# chcp_schematic.net
KiCad netlist of a schematic drawn in EAGLE
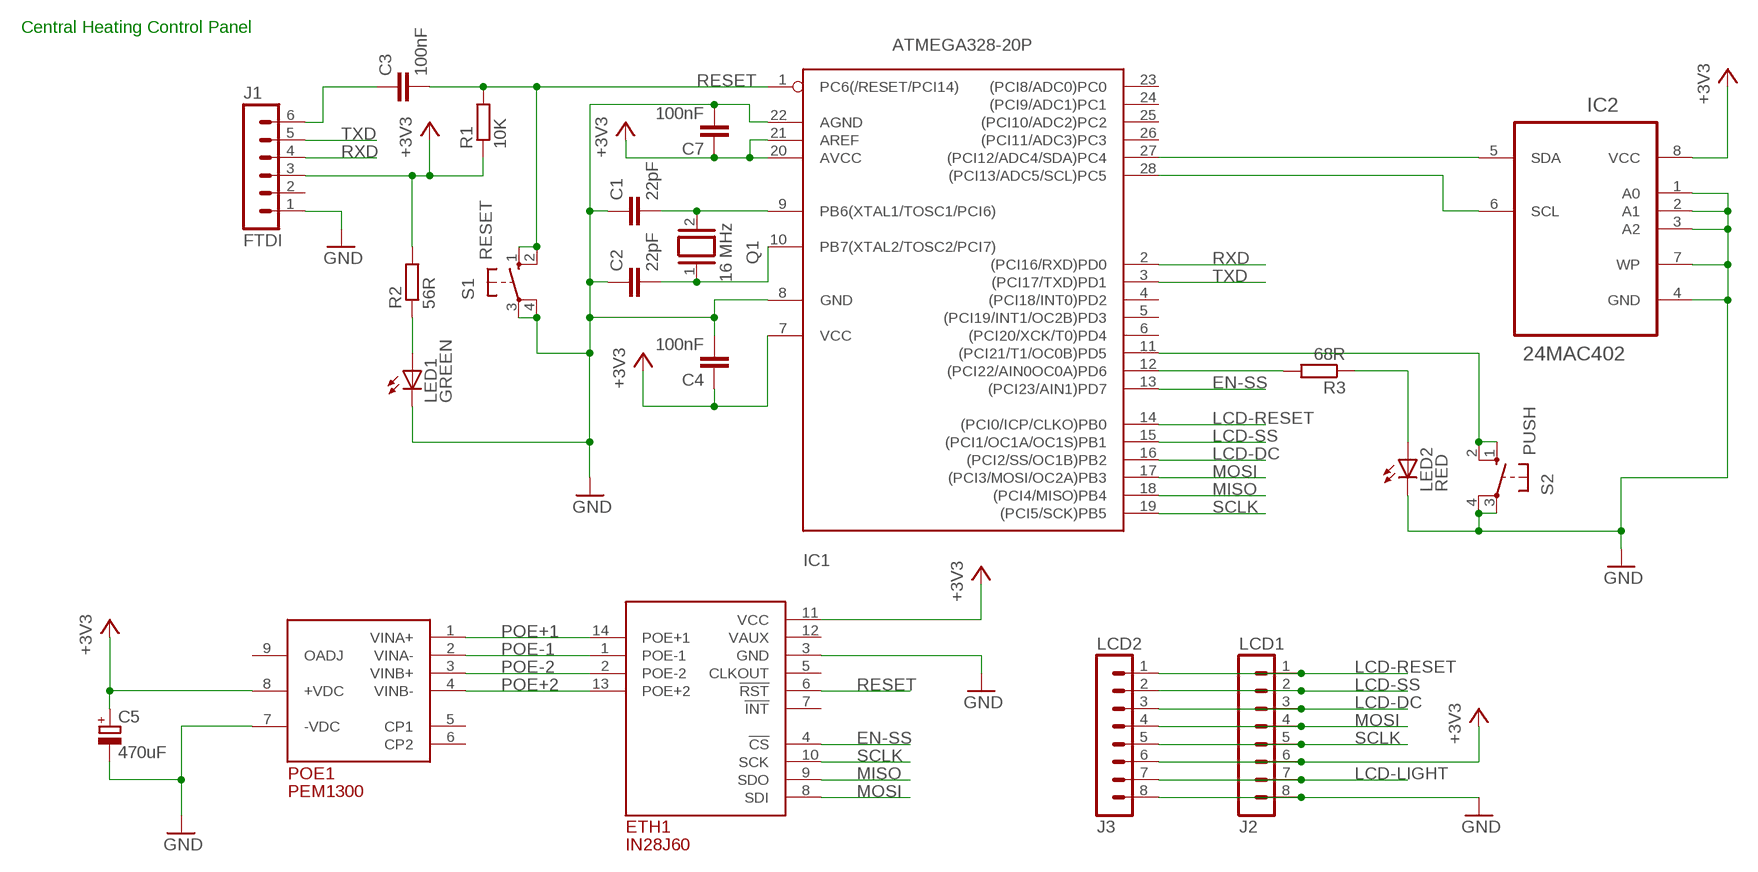
[diagram p0: schematic, sheet 1]

(export (version "E")
  (design (tool "Eeschema 10.0.6"))
  (components
    (comp (ref "C1")
      (value "22pF")
      (footprint "eagle-import:C025-024X044")
      (libsource (lib "eagle-import") (part "C-EU025-024X044"))
    )
    (comp (ref "C2")
      (value "22pF")
      (footprint "eagle-import:C025-024X044")
      (libsource (lib "eagle-import") (part "C-EU025-024X044"))
    )
    (comp (ref "C3")
      (value "100nF")
      (footprint "eagle-import:C025-024X044")
      (libsource (lib "eagle-import") (part "C-EU025-024X044"))
    )
    (comp (ref "C4")
      (value "100nF")
      (footprint "eagle-import:C025-024X044")
      (libsource (lib "eagle-import") (part "C-EU025-024X044"))
    )
    (comp (ref "C5")
      (value "470uF")
      (footprint "eagle-import:E2,5-5")
      (libsource (lib "eagle-import") (part "CPOL-EUE2.5-5"))
    )
    (comp (ref "C7")
      (value "100nF")
      (footprint "eagle-import:C025-024X044")
      (libsource (lib "eagle-import") (part "C-EU025-024X044"))
    )
    (comp (ref "ETH1")
      (value "IN28J60")
      (footprint "eagle-import:DIL")
      (libsource (lib "eagle-import") (part "IN28J60"))
    )
    (comp (ref "IC1")
      (value "ATMEGA328-20P")
      (footprint "eagle-import:DIL28-3")
      (libsource (lib "eagle-import") (part "ATMEGA328P-20"))
    )
    (comp (ref "IC2")
      (value "24MAC402")
      (footprint "eagle-import:PDIP")
      (libsource (lib "eagle-import") (part "24MAC402-SSHM-TPDIP"))
    )
    (comp (ref "J1")
      (value "FTDI")
      (footprint "eagle-import:MA06-1")
      (libsource (lib "eagle-import") (part "MA06-1"))
    )
    (comp (ref "J2")
      (value "LCD1")
      (footprint "eagle-import:MA08-1")
      (libsource (lib "eagle-import") (part "MA08-1"))
    )
    (comp (ref "J3")
      (value "LCD2")
      (footprint "eagle-import:MA08-1")
      (libsource (lib "eagle-import") (part "MA08-1"))
    )
    (comp (ref "LED1")
      (value "GREEN")
      (footprint "eagle-import:LED3MM")
      (libsource (lib "eagle-import") (part "LED3MM"))
    )
    (comp (ref "LED2")
      (value "RED")
      (footprint "eagle-import:LED3MM")
      (libsource (lib "eagle-import") (part "LED3MM"))
    )
    (comp (ref "POE1")
      (value "PEM1300")
      (footprint "eagle-import:SIL")
      (fields (field (name "MPN") "PEM1303"))
      (libsource (lib "eagle-import") (part "PEM1300"))
    )
    (comp (ref "Q1")
      (value "16 MHz")
      (footprint "eagle-import:QS")
      (libsource (lib "eagle-import") (part "XTAL/S"))
    )
    (comp (ref "R1")
      (value "10K")
      (footprint "eagle-import:0204_7")
      (libsource (lib "eagle-import") (part "R-EU_0204/7"))
    )
    (comp (ref "R2")
      (value "56R")
      (footprint "eagle-import:0204_7")
      (libsource (lib "eagle-import") (part "R-EU_0204/7"))
    )
    (comp (ref "R3")
      (value "68R")
      (footprint "eagle-import:0204_7")
      (libsource (lib "eagle-import") (part "R-EU_0204/7"))
    )
    (comp (ref "S1")
      (value "RESET")
      (footprint "eagle-import:B3F-10XX")
      (fields (field (name "MPN") "B3F-1000"))
      (libsource (lib "eagle-import") (part "10-XX"))
    )
    (comp (ref "S2")
      (value "PUSH")
      (footprint "eagle-import:B3F-10XX")
      (fields (field (name "MPN") "B3F-1000"))
      (libsource (lib "eagle-import") (part "10-XX"))
    )
  )
  (nets
    (net (code "1") (name "+3V3") (class "Default")
      (node (ref "C4") (pin "1") (pinfunction "1_1") (pintype "passive"))
      (node (ref "C5") (pin "+") (pinfunction "+_+") (pintype "passive"))
      (node (ref "C7") (pin "1") (pinfunction "1_1") (pintype "passive"))
      (node (ref "ETH1") (pin "11") (pinfunction "VCC_11") (pintype "power_in"))
      (node (ref "IC1") (pin "20") (pinfunction "AVCC_20") (pintype "bidirectional"))
      (node (ref "IC1") (pin "21") (pinfunction "AREF_21") (pintype "bidirectional"))
      (node (ref "IC1") (pin "7") (pinfunction "VCC_7") (pintype "bidirectional"))
      (node (ref "IC2") (pin "8") (pinfunction "VCC_8") (pintype "power_in"))
      (node (ref "J1") (pin "3") (pinfunction "3_3") (pintype "passive"))
      (node (ref "J2") (pin "6") (pinfunction "6_6") (pintype "passive"))
      (node (ref "J3") (pin "6") (pinfunction "6_6") (pintype "passive"))
      (node (ref "POE1") (pin "8") (pinfunction "+VDC_8") (pintype "power_in"))
      (node (ref "R1") (pin "1") (pinfunction "1_1") (pintype "passive"))
      (node (ref "R2") (pin "2") (pinfunction "2_2") (pintype "passive"))
    )
    (net (code "2") (name "/EN-SS") (class "Default")
      (node (ref "ETH1") (pin "4") (pinfunction "~{CS}_4") (pintype "input"))
      (node (ref "IC1") (pin "13") (pinfunction "(PCI23/AIN1)PD7_13") (pintype "bidirectional"))
    )
    (net (code "3") (name "/LCD-DC") (class "Default")
      (node (ref "IC1") (pin "16") (pinfunction "(PCI2/SS/OC1B)PB2_16") (pintype "bidirectional"))
      (node (ref "J2") (pin "3") (pinfunction "3_3") (pintype "passive"))
      (node (ref "J3") (pin "3") (pinfunction "3_3") (pintype "passive"))
    )
    (net (code "4") (name "/LCD-LIGHT") (class "Default")
      (node (ref "J2") (pin "7") (pinfunction "7_7") (pintype "passive"))
      (node (ref "J3") (pin "7") (pinfunction "7_7") (pintype "passive"))
    )
    (net (code "5") (name "/LCD-RESET") (class "Default")
      (node (ref "IC1") (pin "14") (pinfunction "(PCI0/ICP/CLKO)PB0_14") (pintype "bidirectional"))
      (node (ref "J2") (pin "1") (pinfunction "1_1") (pintype "passive"))
      (node (ref "J3") (pin "1") (pinfunction "1_1") (pintype "passive"))
    )
    (net (code "6") (name "/LCD-SS") (class "Default")
      (node (ref "IC1") (pin "15") (pinfunction "(PCI1/OC1A/OC1S)PB1_15") (pintype "bidirectional"))
      (node (ref "J2") (pin "2") (pinfunction "2_2") (pintype "passive"))
      (node (ref "J3") (pin "2") (pinfunction "2_2") (pintype "passive"))
    )
    (net (code "7") (name "/MISO") (class "Default")
      (node (ref "ETH1") (pin "9") (pinfunction "SDO_9") (pintype "output"))
      (node (ref "IC1") (pin "18") (pinfunction "(PCI4/MISO)PB4_18") (pintype "bidirectional"))
    )
    (net (code "8") (name "/MOSI") (class "Default")
      (node (ref "ETH1") (pin "8") (pinfunction "SDI_8") (pintype "input"))
      (node (ref "IC1") (pin "17") (pinfunction "(PCI3/MOSI/OC2A)PB3_17") (pintype "bidirectional"))
      (node (ref "J2") (pin "4") (pinfunction "4_4") (pintype "passive"))
      (node (ref "J3") (pin "4") (pinfunction "4_4") (pintype "passive"))
    )
    (net (code "9") (name "/POE+1") (class "Default")
      (node (ref "ETH1") (pin "14") (pinfunction "POE+1_14") (pintype "output"))
      (node (ref "POE1") (pin "1") (pinfunction "VINA+_1") (pintype "input"))
    )
    (net (code "10") (name "/POE+2") (class "Default")
      (node (ref "ETH1") (pin "13") (pinfunction "POE+2_13") (pintype "output"))
      (node (ref "POE1") (pin "4") (pinfunction "VINB-_4") (pintype "input"))
    )
    (net (code "11") (name "/POE-1") (class "Default")
      (node (ref "ETH1") (pin "1") (pinfunction "POE-1_1") (pintype "output"))
      (node (ref "POE1") (pin "2") (pinfunction "VINA-_2") (pintype "input"))
    )
    (net (code "12") (name "/POE-2") (class "Default")
      (node (ref "ETH1") (pin "2") (pinfunction "POE-2_2") (pintype "output"))
      (node (ref "POE1") (pin "3") (pinfunction "VINB+_3") (pintype "input"))
    )
    (net (code "13") (name "/RESET") (class "Default")
      (node (ref "C3") (pin "2") (pinfunction "2_2") (pintype "passive"))
      (node (ref "ETH1") (pin "6") (pinfunction "~{RST}_6") (pintype "input"))
      (node (ref "IC1") (pin "1") (pinfunction "PC6(/RESET/PCI14)_1") (pintype "bidirectional"))
      (node (ref "R1") (pin "2") (pinfunction "2_2") (pintype "passive"))
      (node (ref "S1") (pin "1") (pinfunction "S_1") (pintype "passive"))
      (node (ref "S1") (pin "2") (pinfunction "S1_2") (pintype "passive"))
    )
    (net (code "14") (name "/RXD") (class "Default")
      (node (ref "IC1") (pin "2") (pinfunction "(PCI16/RXD)PD0_2") (pintype "bidirectional"))
      (node (ref "J1") (pin "4") (pinfunction "4_4") (pintype "passive"))
    )
    (net (code "15") (name "/SCLK") (class "Default")
      (node (ref "ETH1") (pin "10") (pinfunction "SCK_10") (pintype "input"))
      (node (ref "IC1") (pin "19") (pinfunction "(PCI5/SCK)PB5_19") (pintype "bidirectional"))
      (node (ref "J2") (pin "5") (pinfunction "5_5") (pintype "passive"))
      (node (ref "J3") (pin "5") (pinfunction "5_5") (pintype "passive"))
    )
    (net (code "16") (name "/TXD") (class "Default")
      (node (ref "IC1") (pin "3") (pinfunction "(PCI17/TXD)PD1_3") (pintype "bidirectional"))
      (node (ref "J1") (pin "5") (pinfunction "5_5") (pintype "passive"))
    )
    (net (code "17") (name "GND") (class "Default")
      (node (ref "C1") (pin "1") (pinfunction "1_1") (pintype "passive"))
      (node (ref "C2") (pin "1") (pinfunction "1_1") (pintype "passive"))
      (node (ref "C4") (pin "2") (pinfunction "2_2") (pintype "passive"))
      (node (ref "C5") (pin "-") (pinfunction "-_-") (pintype "passive"))
      (node (ref "C7") (pin "2") (pinfunction "2_2") (pintype "passive"))
      (node (ref "ETH1") (pin "3") (pinfunction "GND_3") (pintype "power_in"))
      (node (ref "IC1") (pin "22") (pinfunction "AGND_22") (pintype "bidirectional"))
      (node (ref "IC1") (pin "8") (pinfunction "GND_8") (pintype "bidirectional"))
      (node (ref "IC2") (pin "1") (pinfunction "A0_1") (pintype "input"))
      (node (ref "IC2") (pin "2") (pinfunction "A1_2") (pintype "input"))
      (node (ref "IC2") (pin "3") (pinfunction "A2_3") (pintype "input"))
      (node (ref "IC2") (pin "4") (pinfunction "GND_4") (pintype "power_in"))
      (node (ref "IC2") (pin "7") (pinfunction "WP_7") (pintype "input"))
      (node (ref "J1") (pin "1") (pinfunction "1_1") (pintype "passive"))
      (node (ref "J2") (pin "8") (pinfunction "8_8") (pintype "passive"))
      (node (ref "J3") (pin "8") (pinfunction "8_8") (pintype "passive"))
      (node (ref "LED1") (pin "K") (pinfunction "C_K") (pintype "passive"))
      (node (ref "LED2") (pin "K") (pinfunction "C_K") (pintype "passive"))
      (node (ref "POE1") (pin "7") (pinfunction "-VDC_7") (pintype "power_in"))
      (node (ref "S1") (pin "3") (pinfunction "P_3") (pintype "passive"))
      (node (ref "S1") (pin "4") (pinfunction "P1_4") (pintype "passive"))
      (node (ref "S2") (pin "3") (pinfunction "P_3") (pintype "passive"))
      (node (ref "S2") (pin "4") (pinfunction "P1_4") (pintype "passive"))
    )
    (net (code "18") (name "Net-(C3-Pad1)") (class "Default")
      (node (ref "C3") (pin "1") (pinfunction "1_1") (pintype "passive"))
      (node (ref "J1") (pin "6") (pinfunction "6_6") (pintype "passive"))
    )
    (net (code "19") (name "Net-(IC1-(PCI12{slash}ADC4{slash}SDA)PC4)") (class "Default")
      (node (ref "IC1") (pin "27") (pinfunction "(PCI12/ADC4/SDA)PC4_27") (pintype "bidirectional"))
      (node (ref "IC2") (pin "5") (pinfunction "SDA_5") (pintype "bidirectional"))
    )
    (net (code "20") (name "Net-(IC1-(PCI13{slash}ADC5{slash}SCL)PC5)") (class "Default")
      (node (ref "IC1") (pin "28") (pinfunction "(PCI13/ADC5/SCL)PC5_28") (pintype "bidirectional"))
      (node (ref "IC2") (pin "6") (pinfunction "SCL_6") (pintype "input"))
    )
    (net (code "21") (name "Net-(IC1-(PCI21{slash}T1{slash}OC0B)PD5)") (class "Default")
      (node (ref "IC1") (pin "11") (pinfunction "(PCI21/T1/OC0B)PD5_11") (pintype "bidirectional"))
      (node (ref "S2") (pin "1") (pinfunction "S_1") (pintype "passive"))
      (node (ref "S2") (pin "2") (pinfunction "S1_2") (pintype "passive"))
    )
    (net (code "22") (name "Net-(IC1-(PCI22{slash}AIN0OC0A)PD6)") (class "Default")
      (node (ref "IC1") (pin "12") (pinfunction "(PCI22/AIN0OC0A)PD6_12") (pintype "bidirectional"))
      (node (ref "R3") (pin "2") (pinfunction "2_2") (pintype "passive"))
    )
    (net (code "23") (name "Net-(IC1-PB6(XTAL1{slash}TOSC1{slash}PCI6))") (class "Default")
      (node (ref "C1") (pin "2") (pinfunction "2_2") (pintype "passive"))
      (node (ref "IC1") (pin "9") (pinfunction "PB6(XTAL1/TOSC1/PCI6)_9") (pintype "bidirectional"))
      (node (ref "Q1") (pin "2") (pinfunction "2_2") (pintype "passive"))
    )
    (net (code "24") (name "Net-(IC1-PB7(XTAL2{slash}TOSC2{slash}PCI7))") (class "Default")
      (node (ref "C2") (pin "2") (pinfunction "2_2") (pintype "passive"))
      (node (ref "IC1") (pin "10") (pinfunction "PB7(XTAL2/TOSC2/PCI7)_10") (pintype "bidirectional"))
      (node (ref "Q1") (pin "1") (pinfunction "1_1") (pintype "passive"))
    )
    (net (code "25") (name "Net-(LED1-PadA)") (class "Default")
      (node (ref "LED1") (pin "A") (pinfunction "A_A") (pintype "passive"))
      (node (ref "R2") (pin "1") (pinfunction "1_1") (pintype "passive"))
    )
    (net (code "26") (name "Net-(LED2-PadA)") (class "Default")
      (node (ref "LED2") (pin "A") (pinfunction "A_A") (pintype "passive"))
      (node (ref "R3") (pin "1") (pinfunction "1_1") (pintype "passive"))
    )
    (net (code "27") (name "unconnected-(ETH1-CLKOUT-Pad5)") (class "Default")
      (node (ref "ETH1") (pin "5") (pinfunction "CLKOUT_5") (pintype "output"))
    )
    (net (code "28") (name "unconnected-(ETH1-VAUX-Pad12)") (class "Default")
      (node (ref "ETH1") (pin "12") (pinfunction "VAUX_12") (pintype "bidirectional"))
    )
    (net (code "29") (name "unconnected-(ETH1-~{INT}-Pad7)") (class "Default")
      (node (ref "ETH1") (pin "7") (pinfunction "~{INT}_7") (pintype "output"))
    )
    (net (code "30") (name "unconnected-(IC1-(PCI8{slash}ADC0)PC0-Pad23)") (class "Default")
      (node (ref "IC1") (pin "23") (pinfunction "(PCI8/ADC0)PC0_23") (pintype "bidirectional"))
    )
    (net (code "31") (name "unconnected-(IC1-(PCI9{slash}ADC1)PC1-Pad24)") (class "Default")
      (node (ref "IC1") (pin "24") (pinfunction "(PCI9/ADC1)PC1_24") (pintype "bidirectional"))
    )
    (net (code "32") (name "unconnected-(IC1-(PCI10{slash}ADC2)PC2-Pad25)") (class "Default")
      (node (ref "IC1") (pin "25") (pinfunction "(PCI10/ADC2)PC2_25") (pintype "bidirectional"))
    )
    (net (code "33") (name "unconnected-(IC1-(PCI11{slash}ADC3)PC3-Pad26)") (class "Default")
      (node (ref "IC1") (pin "26") (pinfunction "(PCI11/ADC3)PC3_26") (pintype "bidirectional"))
    )
    (net (code "34") (name "unconnected-(IC1-(PCI18{slash}INT0)PD2-Pad4)") (class "Default")
      (node (ref "IC1") (pin "4") (pinfunction "(PCI18/INT0)PD2_4") (pintype "bidirectional"))
    )
    (net (code "35") (name "unconnected-(IC1-(PCI19{slash}INT1{slash}OC2B)PD3-Pad5)") (class "Default")
      (node (ref "IC1") (pin "5") (pinfunction "(PCI19/INT1/OC2B)PD3_5") (pintype "bidirectional"))
    )
    (net (code "36") (name "unconnected-(IC1-(PCI20{slash}XCK{slash}T0)PD4-Pad6)") (class "Default")
      (node (ref "IC1") (pin "6") (pinfunction "(PCI20/XCK/T0)PD4_6") (pintype "bidirectional"))
    )
    (net (code "37") (name "unconnected-(J1-Pad2)") (class "Default")
      (node (ref "J1") (pin "2") (pinfunction "2_2") (pintype "passive"))
    )
    (net (code "38") (name "unconnected-(POE1-CP1-Pad5)") (class "Default")
      (node (ref "POE1") (pin "5") (pinfunction "CP1_5") (pintype "bidirectional"))
    )
    (net (code "39") (name "unconnected-(POE1-CP2-Pad6)") (class "Default")
      (node (ref "POE1") (pin "6") (pinfunction "CP2_6") (pintype "bidirectional"))
    )
    (net (code "40") (name "unconnected-(POE1-OADJ-Pad9)") (class "Default")
      (node (ref "POE1") (pin "9") (pinfunction "OADJ_9") (pintype "bidirectional"))
    )
  )
)
